# Connectors.net
KiCad netlist of a schematic drawn in Altium Designer
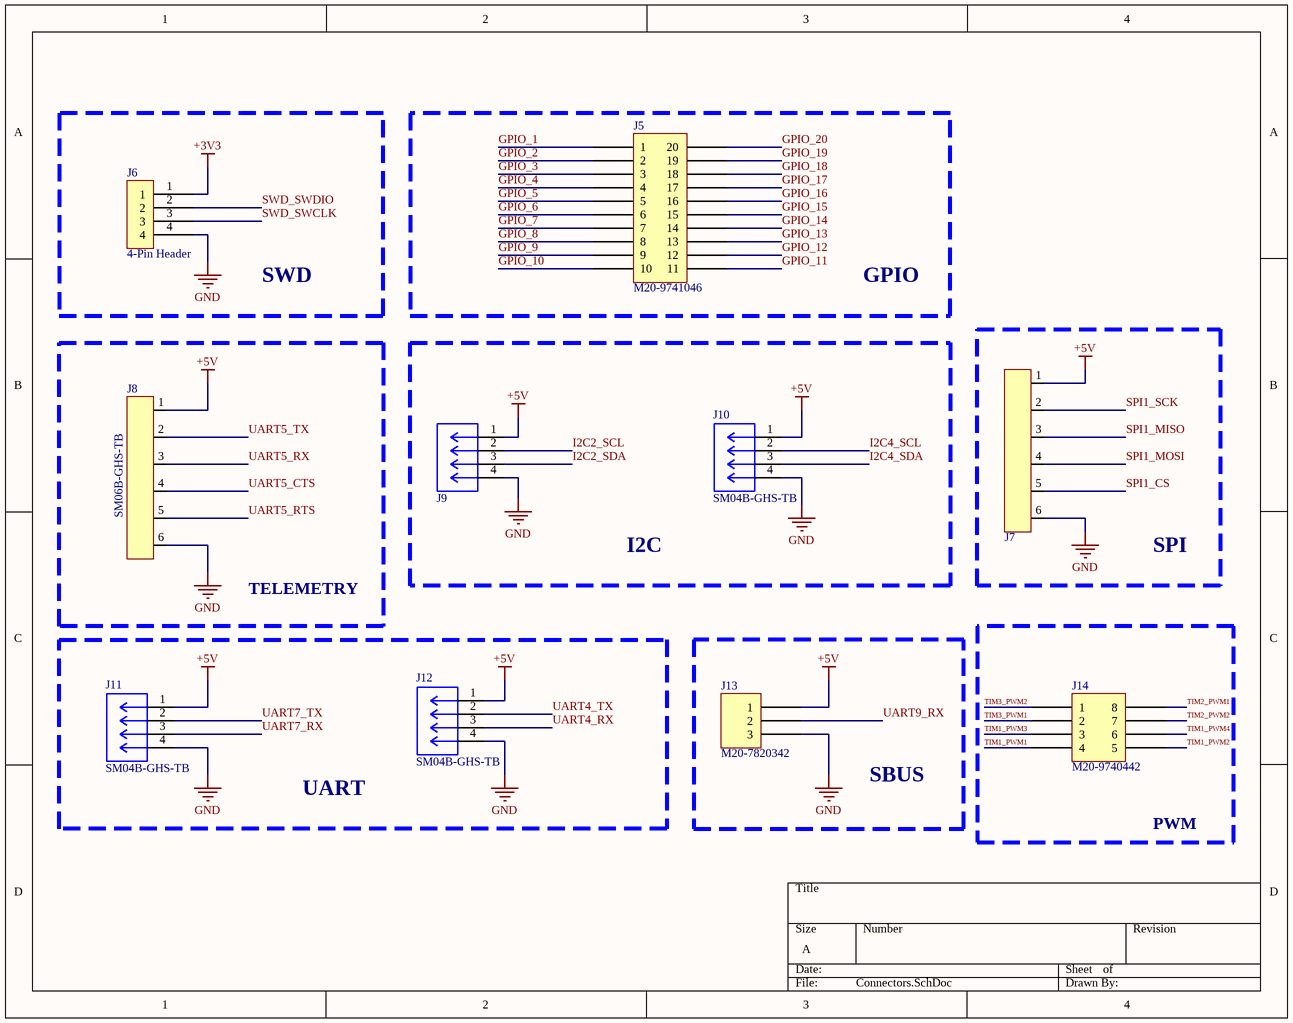
[diagram p0: Connectors.SchDoc]

(export (version "E")
  (design (tool "Eeschema 10.0.6"))
  (components
    (comp (ref "J5")
      (value "M20-9741046")
      (footprint "HARWIN M20-9741045")
      (description "CONN HEADER R/A 20POS 2.54MM")
      (fields (field (name "MANUFACTURER") "Harwin Inc."))
      (libsource (lib "Celestial Altium Library - altium_library (1)") (part "2X10 PIN DU"))
    )
    (comp (ref "J6")
      (value "4-Pin Header")
      (footprint "4-Pin Header")
      (libsource (lib "AltiumSchLib") (part "4-Pin Header"))
    )
    (comp (ref "J7")
      (value "SM06B-GHS-TB")
      (footprint "SM06B-GHS-TB")
      (description "Header Connector 6 Position 1.25MM Pitch SMD Horizontal JST GH")
      (fields (field (name "MANUFACTURER") "JST"))
      (libsource (lib "Schematic-Lib-PhilsLab") (part "SM06B-GHS-TB"))
    )
    (comp (ref "J8")
      (value "SM06B-GHS-TB")
      (footprint "SM06B-GHS-TB")
      (description "Header Connector 6 Position 1.25MM Pitch SMD Horizontal JST GH")
      (fields (field (name "MANUFACTURER") "JST"))
      (libsource (lib "Schematic-Lib-PhilsLab") (part "SM06B-GHS-TB"))
    )
    (comp (ref "J9")
      (value "SM04B-GHS-TB")
      (footprint "CONN_SM04B-GHS-TB_JST")
      (description "Connector Header Surface Mount, Right Angle 4 position 0.049 (1.25mm)")
      (fields (field (name "MF") "JST Sales"))
      (libsource (lib "SM04B-GHS-TB") (part "SM04B-GHS-TB"))
    )
    (comp (ref "J10")
      (value "SM04B-GHS-TB")
      (footprint "CONN_SM04B-GHS-TB_JST")
      (description "Connector Header Surface Mount, Right Angle 4 position 0.049 (1.25mm)")
      (fields (field (name "MF") "JST Sales"))
      (libsource (lib "SM04B-GHS-TB") (part "SM04B-GHS-TB"))
    )
    (comp (ref "J11")
      (value "SM04B-GHS-TB")
      (footprint "CONN_SM04B-GHS-TB_JST")
      (description "Connector Header Surface Mount, Right Angle 4 position 0.049 (1.25mm)")
      (fields (field (name "MF") "JST Sales"))
      (libsource (lib "SM04B-GHS-TB") (part "SM04B-GHS-TB"))
    )
    (comp (ref "J12")
      (value "SM04B-GHS-TB")
      (footprint "CONN_SM04B-GHS-TB_JST")
      (description "Connector Header Surface Mount, Right Angle 4 position 0.049 (1.25mm)")
      (fields (field (name "MF") "JST Sales"))
      (libsource (lib "SM04B-GHS-TB") (part "SM04B-GHS-TB"))
    )
    (comp (ref "J13")
      (value "M20-7820342")
      (footprint "HARWIN M20-7820345")
      (description "CONN RCPT 3POS 0.1 GOLD PCB")
      (fields (field (name "MANUFACTURER") "Harwin Inc."))
      (libsource (lib "Celestial Altium Library - altium_library (1)") (part "3 Pin"))
    )
    (comp (ref "J14")
      (value "M20-9740442")
      (footprint "HARWIN M20-9740445")
      (description "CONN HEADER R/A 8POS 2.54MM")
      (fields (field (name "MANUFACTURER") "Harwin Inc."))
      (libsource (lib "Celestial Altium Library - altium_library (1)") (part "2X4 PIN DU"))
    )
  )
  (nets
    (net (code "1") (name "+3V3") (class "Default")
      (node (ref "J6") (pin "1") (pinfunction "1_1") (pintype "passive"))
    )
    (net (code "2") (name "+5V") (class "Default")
      (node (ref "J10") (pin "1") (pinfunction "1_1") (pintype "passive"))
      (node (ref "J11") (pin "1") (pinfunction "1_1") (pintype "passive"))
      (node (ref "J12") (pin "1") (pinfunction "1_1") (pintype "passive"))
      (node (ref "J13") (pin "1") (pinfunction "1_1") (pintype "passive"))
      (node (ref "J7") (pin "1") (pinfunction "1_1") (pintype "passive"))
      (node (ref "J8") (pin "1") (pinfunction "1_1") (pintype "passive"))
      (node (ref "J9") (pin "1") (pinfunction "1_1") (pintype "passive"))
    )
    (net (code "3") (name "/GPIO_1") (class "Default")
      (node (ref "J5") (pin "1") (pinfunction "1_1") (pintype "passive"))
    )
    (net (code "4") (name "/GPIO_2") (class "Default")
      (node (ref "J5") (pin "2") (pinfunction "2_2") (pintype "passive"))
    )
    (net (code "5") (name "/GPIO_3") (class "Default")
      (node (ref "J5") (pin "3") (pinfunction "3_3") (pintype "passive"))
    )
    (net (code "6") (name "/GPIO_4") (class "Default")
      (node (ref "J5") (pin "4") (pinfunction "4_4") (pintype "passive"))
    )
    (net (code "7") (name "/GPIO_5") (class "Default")
      (node (ref "J5") (pin "5") (pinfunction "5_5") (pintype "passive"))
    )
    (net (code "8") (name "/GPIO_6") (class "Default")
      (node (ref "J5") (pin "6") (pinfunction "6_6") (pintype "passive"))
    )
    (net (code "9") (name "/GPIO_7") (class "Default")
      (node (ref "J5") (pin "7") (pinfunction "7_7") (pintype "passive"))
    )
    (net (code "10") (name "/GPIO_8") (class "Default")
      (node (ref "J5") (pin "8") (pinfunction "8_8") (pintype "passive"))
    )
    (net (code "11") (name "/GPIO_9") (class "Default")
      (node (ref "J5") (pin "9") (pinfunction "9_9") (pintype "passive"))
    )
    (net (code "12") (name "/GPIO_10") (class "Default")
      (node (ref "J5") (pin "10") (pinfunction "10_10") (pintype "passive"))
    )
    (net (code "13") (name "/GPIO_11") (class "Default")
      (node (ref "J5") (pin "11") (pinfunction "11_11") (pintype "passive"))
    )
    (net (code "14") (name "/GPIO_12") (class "Default")
      (node (ref "J5") (pin "12") (pinfunction "12_12") (pintype "passive"))
    )
    (net (code "15") (name "/GPIO_13") (class "Default")
      (node (ref "J5") (pin "13") (pinfunction "13_13") (pintype "passive"))
    )
    (net (code "16") (name "/GPIO_14") (class "Default")
      (node (ref "J5") (pin "14") (pinfunction "14_14") (pintype "passive"))
    )
    (net (code "17") (name "/GPIO_15") (class "Default")
      (node (ref "J5") (pin "15") (pinfunction "15_15") (pintype "passive"))
    )
    (net (code "18") (name "/GPIO_16") (class "Default")
      (node (ref "J5") (pin "16") (pinfunction "16_16") (pintype "passive"))
    )
    (net (code "19") (name "/GPIO_17") (class "Default")
      (node (ref "J5") (pin "17") (pinfunction "17_17") (pintype "passive"))
    )
    (net (code "20") (name "/GPIO_18") (class "Default")
      (node (ref "J5") (pin "18") (pinfunction "18_18") (pintype "passive"))
    )
    (net (code "21") (name "/GPIO_19") (class "Default")
      (node (ref "J5") (pin "19") (pinfunction "19_19") (pintype "passive"))
    )
    (net (code "22") (name "/GPIO_20") (class "Default")
      (node (ref "J5") (pin "20") (pinfunction "20_20") (pintype "passive"))
    )
    (net (code "23") (name "/I2C2_SCL") (class "Default")
      (node (ref "J9") (pin "2") (pinfunction "2_2") (pintype "passive"))
    )
    (net (code "24") (name "/I2C2_SDA") (class "Default")
      (node (ref "J9") (pin "3") (pinfunction "3_3") (pintype "passive"))
    )
    (net (code "25") (name "/I2C4_SCL") (class "Default")
      (node (ref "J10") (pin "2") (pinfunction "2_2") (pintype "passive"))
    )
    (net (code "26") (name "/I2C4_SDA") (class "Default")
      (node (ref "J10") (pin "3") (pinfunction "3_3") (pintype "passive"))
    )
    (net (code "27") (name "/SPI1_CS") (class "Default")
      (node (ref "J7") (pin "5") (pinfunction "5_5") (pintype "passive"))
    )
    (net (code "28") (name "/SPI1_MISO") (class "Default")
      (node (ref "J7") (pin "3") (pinfunction "3_3") (pintype "passive"))
    )
    (net (code "29") (name "/SPI1_MOSI") (class "Default")
      (node (ref "J7") (pin "4") (pinfunction "4_4") (pintype "passive"))
    )
    (net (code "30") (name "/SPI1_SCK") (class "Default")
      (node (ref "J7") (pin "2") (pinfunction "2_2") (pintype "passive"))
    )
    (net (code "31") (name "/SWD_SWCLK") (class "Default")
      (node (ref "J6") (pin "3") (pinfunction "3_3") (pintype "passive"))
    )
    (net (code "32") (name "/SWD_SWDIO") (class "Default")
      (node (ref "J6") (pin "2") (pinfunction "2_2") (pintype "passive"))
    )
    (net (code "33") (name "/TIM1_PWM1") (class "Default")
      (node (ref "J14") (pin "4") (pinfunction "4_4") (pintype "passive"))
    )
    (net (code "34") (name "/TIM1_PWM2") (class "Default")
      (node (ref "J14") (pin "5") (pinfunction "5_5") (pintype "passive"))
    )
    (net (code "35") (name "/TIM1_PWM3") (class "Default")
      (node (ref "J14") (pin "3") (pinfunction "3_3") (pintype "passive"))
    )
    (net (code "36") (name "/TIM1_PWM4") (class "Default")
      (node (ref "J14") (pin "6") (pinfunction "6_6") (pintype "passive"))
    )
    (net (code "37") (name "/TIM2_PWM1") (class "Default")
      (node (ref "J14") (pin "8") (pinfunction "8_8") (pintype "passive"))
    )
    (net (code "38") (name "/TIM2_PWM2") (class "Default")
      (node (ref "J14") (pin "7") (pinfunction "7_7") (pintype "passive"))
    )
    (net (code "39") (name "/TIM3_PWM1") (class "Default")
      (node (ref "J14") (pin "2") (pinfunction "2_2") (pintype "passive"))
    )
    (net (code "40") (name "/TIM3_PWM2") (class "Default")
      (node (ref "J14") (pin "1") (pinfunction "1_1") (pintype "passive"))
    )
    (net (code "41") (name "/UART4_RX") (class "Default")
      (node (ref "J12") (pin "3") (pinfunction "3_3") (pintype "passive"))
    )
    (net (code "42") (name "/UART4_TX") (class "Default")
      (node (ref "J12") (pin "2") (pinfunction "2_2") (pintype "passive"))
    )
    (net (code "43") (name "/UART5_CTS") (class "Default")
      (node (ref "J8") (pin "4") (pinfunction "4_4") (pintype "passive"))
    )
    (net (code "44") (name "/UART5_RTS") (class "Default")
      (node (ref "J8") (pin "5") (pinfunction "5_5") (pintype "passive"))
    )
    (net (code "45") (name "/UART5_RX") (class "Default")
      (node (ref "J8") (pin "3") (pinfunction "3_3") (pintype "passive"))
    )
    (net (code "46") (name "/UART5_TX") (class "Default")
      (node (ref "J8") (pin "2") (pinfunction "2_2") (pintype "passive"))
    )
    (net (code "47") (name "/UART7_RX") (class "Default")
      (node (ref "J11") (pin "3") (pinfunction "3_3") (pintype "passive"))
    )
    (net (code "48") (name "/UART7_TX") (class "Default")
      (node (ref "J11") (pin "2") (pinfunction "2_2") (pintype "passive"))
    )
    (net (code "49") (name "/UART9_RX") (class "Default")
      (node (ref "J13") (pin "2") (pinfunction "2_2") (pintype "passive"))
    )
    (net (code "50") (name "GND") (class "Default")
      (node (ref "J10") (pin "4") (pinfunction "4_4") (pintype "passive"))
      (node (ref "J11") (pin "4") (pinfunction "4_4") (pintype "passive"))
      (node (ref "J12") (pin "4") (pinfunction "4_4") (pintype "passive"))
      (node (ref "J13") (pin "3") (pinfunction "3_3") (pintype "passive"))
      (node (ref "J6") (pin "4") (pinfunction "4_4") (pintype "passive"))
      (node (ref "J7") (pin "6") (pinfunction "6_6") (pintype "passive"))
      (node (ref "J8") (pin "6") (pinfunction "6_6") (pintype "passive"))
      (node (ref "J9") (pin "4") (pinfunction "4_4") (pintype "passive"))
    )
  )
)
